# TarjetaMicrofono.net
KiCad netlist of a schematic drawn in Altium Designer
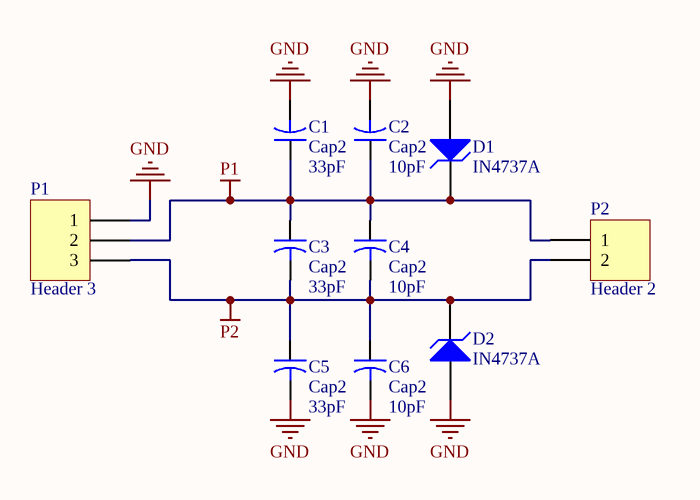
[diagram p0: TarjetaMicrofono.SchDoc]

(export (version "E")
  (design (tool "Eeschema 10.0.6"))
  (components
    (comp (ref "C1")
      (value "Cap2")
      (footprint "CAPR5-4X5")
      (description "Capacitor")
      (fields (field (name "ALTIUM_VALUE") "33pF") (field (name "PUBLISHER") "Altium Limited"))
      (libsource (lib "Miscellaneous Devices") (part "Cap2"))
    )
    (comp (ref "C2")
      (value "Cap2")
      (footprint "CAPR5-4X5")
      (description "Capacitor")
      (fields (field (name "ALTIUM_VALUE") "10pF") (field (name "PUBLISHER") "Altium Limited"))
      (libsource (lib "Miscellaneous Devices") (part "Cap2"))
    )
    (comp (ref "C3")
      (value "Cap2")
      (footprint "CAPR5-4X5")
      (description "Capacitor")
      (fields (field (name "ALTIUM_VALUE") "33pF") (field (name "PUBLISHER") "Altium Limited"))
      (libsource (lib "Miscellaneous Devices") (part "Cap2"))
    )
    (comp (ref "C4")
      (value "Cap2")
      (footprint "CAPR5-4X5")
      (description "Capacitor")
      (fields (field (name "ALTIUM_VALUE") "10pF") (field (name "PUBLISHER") "Altium Limited"))
      (libsource (lib "Miscellaneous Devices") (part "Cap2"))
    )
    (comp (ref "C5")
      (value "Cap2")
      (footprint "CAPR5-4X5")
      (description "Capacitor")
      (fields (field (name "ALTIUM_VALUE") "33pF") (field (name "PUBLISHER") "Altium Limited"))
      (libsource (lib "Miscellaneous Devices") (part "Cap2"))
    )
    (comp (ref "C6")
      (value "Cap2")
      (footprint "CAPR5-4X5")
      (description "Capacitor")
      (fields (field (name "ALTIUM_VALUE") "10pF") (field (name "PUBLISHER") "Altium Limited"))
      (libsource (lib "Miscellaneous Devices") (part "Cap2"))
    )
    (comp (ref "D1")
      (value "IN4737A")
      (footprint "DIODE-0.7")
      (description "Zener Diode")
      (fields (field (name "PUBLISHER") "Altium Limited"))
      (libsource (lib "Miscellaneous Devices") (part "D Zener"))
    )
    (comp (ref "D2")
      (value "IN4737A")
      (footprint "DIODE-0.7")
      (description "Zener Diode")
      (fields (field (name "PUBLISHER") "Altium Limited"))
      (libsource (lib "Miscellaneous Devices") (part "D Zener"))
    )
    (comp (ref "P1")
      (value "Header 3")
      (footprint "HDR1X3")
      (description "Header, 3-Pin")
      (fields (field (name "PUBLISHER") "Altium Limited"))
      (libsource (lib "Miscellaneous Connectors") (part "Header 3"))
    )
    (comp (ref "P2")
      (value "Header 2")
      (footprint "HDR1X2")
      (description "Header, 2-Pin")
      (fields (field (name "PUBLISHER") "Altium Limited"))
      (libsource (lib "Miscellaneous Connectors") (part "Header 2"))
    )
  )
  (nets
    (net (code "1") (name "GND") (class "Default")
      (node (ref "C1") (pin "2") (pinfunction "2_2") (pintype "passive"))
      (node (ref "C2") (pin "2") (pinfunction "2_2") (pintype "passive"))
      (node (ref "C5") (pin "2") (pinfunction "2_2") (pintype "passive"))
      (node (ref "C6") (pin "2") (pinfunction "2_2") (pintype "passive"))
      (node (ref "D1") (pin "1") (pinfunction "A_1") (pintype "passive"))
      (node (ref "D2") (pin "1") (pinfunction "A_1") (pintype "passive"))
      (node (ref "P1") (pin "1") (pinfunction "1_1") (pintype "passive"))
    )
    (net (code "2") (name "P1") (class "Default")
      (node (ref "C1") (pin "1") (pinfunction "1_1") (pintype "passive"))
      (node (ref "C2") (pin "1") (pinfunction "1_1") (pintype "passive"))
      (node (ref "C3") (pin "1") (pinfunction "1_1") (pintype "passive"))
      (node (ref "C4") (pin "1") (pinfunction "1_1") (pintype "passive"))
      (node (ref "D1") (pin "2") (pinfunction "K_2") (pintype "passive"))
      (node (ref "P1") (pin "2") (pinfunction "2_2") (pintype "passive"))
      (node (ref "P2") (pin "1") (pinfunction "1_1") (pintype "passive"))
    )
    (net (code "3") (name "P2") (class "Default")
      (node (ref "C3") (pin "2") (pinfunction "2_2") (pintype "passive"))
      (node (ref "C4") (pin "2") (pinfunction "2_2") (pintype "passive"))
      (node (ref "C5") (pin "1") (pinfunction "1_1") (pintype "passive"))
      (node (ref "C6") (pin "1") (pinfunction "1_1") (pintype "passive"))
      (node (ref "D2") (pin "2") (pinfunction "K_2") (pintype "passive"))
      (node (ref "P1") (pin "3") (pinfunction "3_3") (pintype "passive"))
      (node (ref "P2") (pin "2") (pinfunction "2_2") (pintype "passive"))
    )
  )
)
